# ShiftRegister.net
KiCad netlist of a schematic drawn in Altium Designer
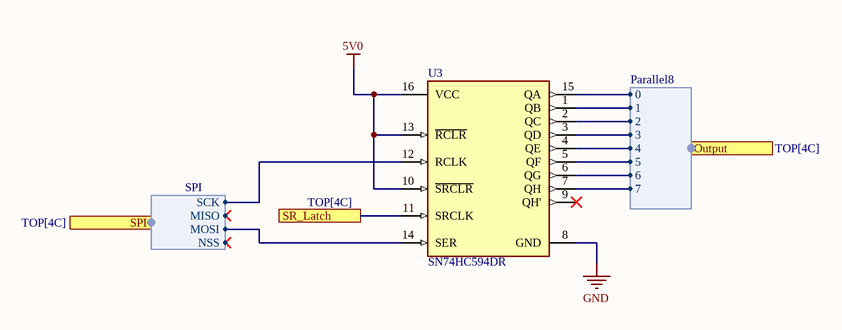
[diagram p0: ShiftRegister.SchDoc]

(export (version "E")
  (design (tool "Eeschema 10.0.6"))
  (components
    (comp (ref "U3")
      (value "SN74HC594DR")
      (footprint "FP-D0016A-IPC_A")
      (description "IC SHIFT REGISTER 8BIT 16-SOIC")
      (libsource (lib "Altium Content Vault") (part "6ffdf0eb1487316571b39b71ede2db7"))
    )
  )
  (nets
    (net (code "3") (name "/0") (class "Default")
      (node (ref "U3") (pin "15") (pinfunction "QA_15") (pintype "output"))
    )
    (net (code "4") (name "/1") (class "Default")
      (node (ref "U3") (pin "1") (pinfunction "QB_1") (pintype "output"))
    )
    (net (code "5") (name "/2") (class "Default")
      (node (ref "U3") (pin "2") (pinfunction "QC_2") (pintype "output"))
    )
    (net (code "6") (name "/3") (class "Default")
      (node (ref "U3") (pin "3") (pinfunction "QD_3") (pintype "output"))
    )
    (net (code "7") (name "/4") (class "Default")
      (node (ref "U3") (pin "4") (pinfunction "QE_4") (pintype "output"))
    )
    (net (code "8") (name "/5") (class "Default")
      (node (ref "U3") (pin "5") (pinfunction "QF_5") (pintype "output"))
    )
    (net (code "9") (name "/6") (class "Default")
      (node (ref "U3") (pin "6") (pinfunction "QG_6") (pintype "output"))
    )
    (net (code "10") (name "/7") (class "Default")
      (node (ref "U3") (pin "7") (pinfunction "QH_7") (pintype "output"))
    )
    (net (code "11") (name "/MOSI") (class "Default")
      (node (ref "U3") (pin "14") (pinfunction "SER_14") (pintype "input"))
    )
    (net (code "12") (name "/SCK") (class "Default")
      (node (ref "U3") (pin "12") (pinfunction "RCLK_12") (pintype "input"))
    )
    (net (code "13") (name "/SR_Latch") (class "Default")
      (node (ref "U3") (pin "11") (pinfunction "SRCLK_11") (pintype "input"))
    )
    (net (code "16") (name "5V0") (class "Default")
      (node (ref "U3") (pin "10") (pinfunction "~{SRCLR}_10") (pintype "input"))
      (node (ref "U3") (pin "13") (pinfunction "~{RCLR}_13") (pintype "input"))
      (node (ref "U3") (pin "16") (pinfunction "VCC_16") (pintype "power_in"))
    )
    (net (code "17") (name "GND") (class "Default")
      (node (ref "U3") (pin "8") (pinfunction "GND_8") (pintype "power_in"))
    )
    (net (code "18") (name "unconnected-(U3-QH'-Pad9)") (class "Default")
      (node (ref "U3") (pin "9") (pinfunction "QH'_9") (pintype "output+no_connect"))
    )
  )
)
